# Sensor.net
KiCad netlist of a schematic drawn in Altium Designer
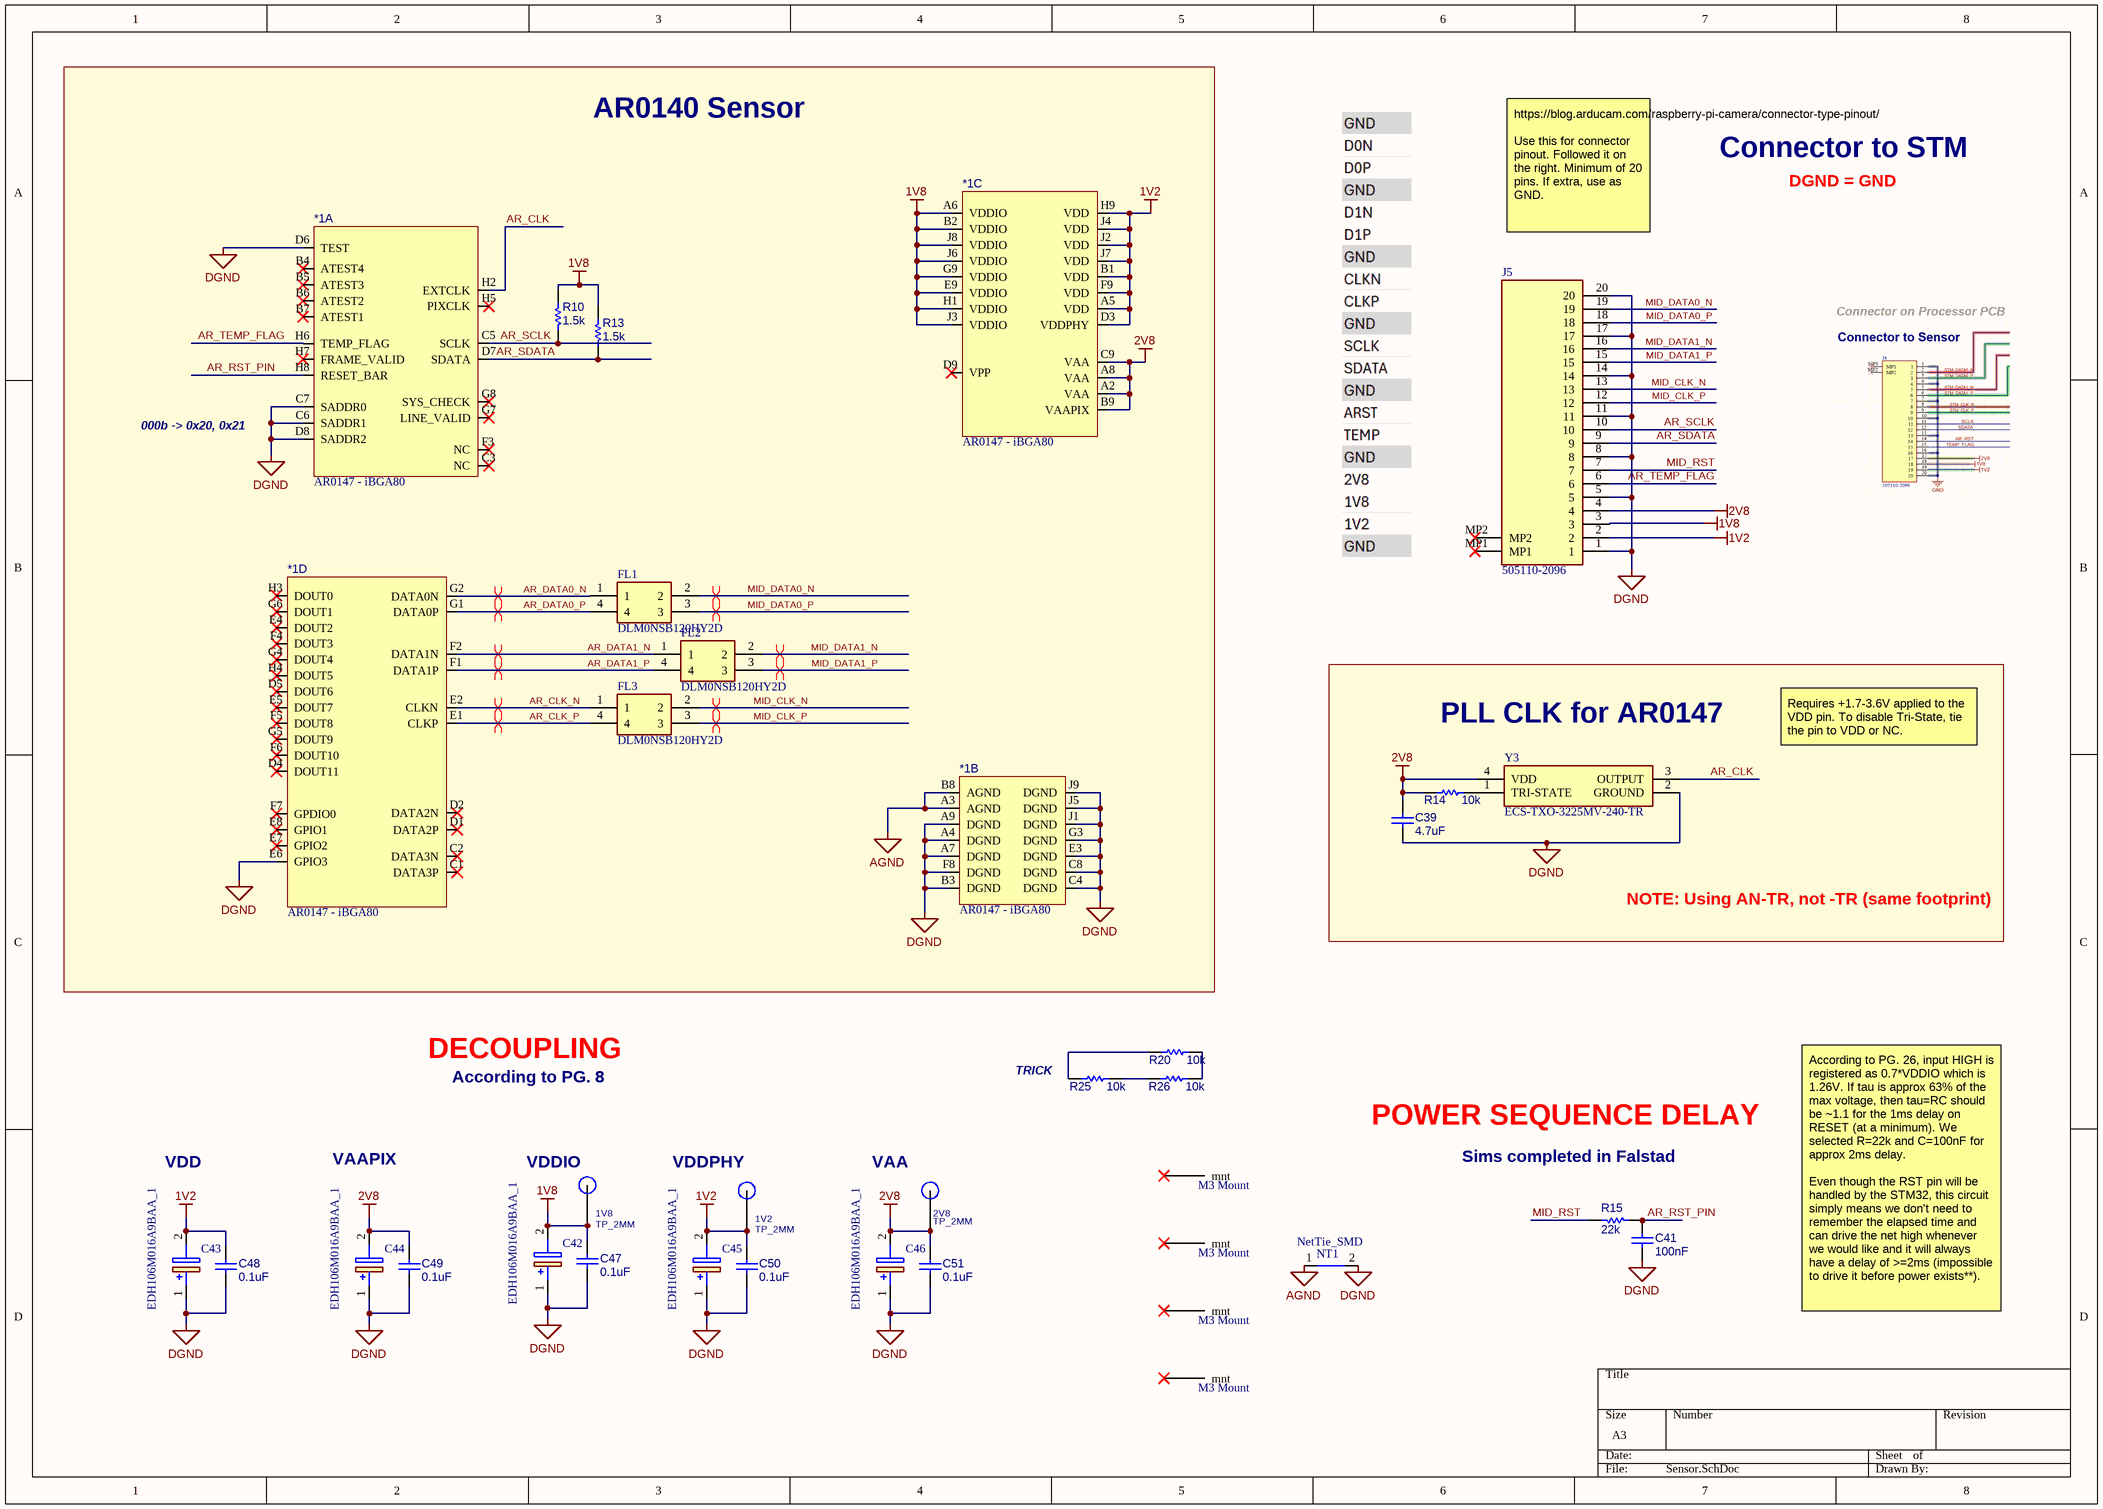
[diagram p0: Sensor.SchDoc]

(export (version "E")
  (design (tool "Eeschema 10.0.6"))
  (components
    (comp (ref "*1")
      (value "AR0147 - iBGA80")
      (footprint "AR0147 - IBGA80")
      (libsource (lib "C2S") (part "AR0147 - iBGA80"))
    )
    (comp (ref "1V2")
      (value "TP_2MM")
      (footprint "TESTPOINT 2MM")
      (libsource (lib "C2Sv0 - Processor") (part "TP_2MM"))
    )
    (comp (ref "1V8")
      (value "TP_2MM")
      (footprint "TESTPOINT 2MM")
      (libsource (lib "C2Sv0 - Processor") (part "TP_2MM"))
    )
    (comp (ref "2V8")
      (value "TP_2MM")
      (footprint "TESTPOINT 2MM")
      (libsource (lib "C2Sv0 - Processor") (part "TP_2MM"))
    )
    (comp (ref "C39")
      (value "4.7uF")
      (footprint "C0603")
      (description "Capacitor, MLCC, 100nF, 6V3, X5R, 10%, 0603, T=0,8mm")
      (fields
        (field (name "MANUFACTURER PART NUMBER") "CC0603KRX5R5BB104")
        (field (name "MANUFACTURER") "YAGEO")
        (field (name "PROVIDED_BY") "SUBCO")
      )
      (libsource (lib "Perth Aerospace Student Team") (part "CMP-035-000015-1"))
    )
    (comp (ref "C41")
      (value "100nF")
      (footprint "C0603")
      (description "Capacitor, MLCC, 100nF, 6V3, X5R, 10%, 0603, T=0,8mm")
      (fields
        (field (name "MANUFACTURER PART NUMBER") "CC0603KRX5R5BB104")
        (field (name "MANUFACTURER") "YAGEO")
        (field (name "PROVIDED_BY") "SUBCO")
      )
      (libsource (lib "Perth Aerospace Student Team") (part "CMP-035-000015-1"))
    )
    (comp (ref "C42")
      (value "EDH106M016A9BAA_1")
      (footprint "EDH106M016A9BAA")
      (description "Capacitor Polarised")
      (fields
        (field (name "MANUFACTURER_PART_NUMBER") "EDH106M016A9BAA")
        (field (name "MOUSER PART NUMBER") "80-EDH106M016A9BAA")
      )
      (libsource (lib "C2Sv0 - Processor") (part "EDH106M016A9BAA_1"))
    )
    (comp (ref "C43")
      (value "EDH106M016A9BAA_1")
      (footprint "EDH106M016A9BAA")
      (description "Capacitor Polarised")
      (fields
        (field (name "MANUFACTURER_PART_NUMBER") "EDH106M016A9BAA")
        (field (name "MOUSER PART NUMBER") "80-EDH106M016A9BAA")
      )
      (libsource (lib "C2Sv0 - Processor") (part "EDH106M016A9BAA_1"))
    )
    (comp (ref "C44")
      (value "EDH106M016A9BAA_1")
      (footprint "EDH106M016A9BAA")
      (description "Capacitor Polarised")
      (fields
        (field (name "MANUFACTURER_PART_NUMBER") "EDH106M016A9BAA")
        (field (name "MOUSER PART NUMBER") "80-EDH106M016A9BAA")
      )
      (libsource (lib "C2Sv0 - Processor") (part "EDH106M016A9BAA_1"))
    )
    (comp (ref "C45")
      (value "EDH106M016A9BAA_1")
      (footprint "EDH106M016A9BAA")
      (description "Capacitor Polarised")
      (fields
        (field (name "MANUFACTURER_PART_NUMBER") "EDH106M016A9BAA")
        (field (name "MOUSER PART NUMBER") "80-EDH106M016A9BAA")
      )
      (libsource (lib "C2Sv0 - Processor") (part "EDH106M016A9BAA_1"))
    )
    (comp (ref "C46")
      (value "EDH106M016A9BAA_1")
      (footprint "EDH106M016A9BAA")
      (description "Capacitor Polarised")
      (fields
        (field (name "MANUFACTURER_PART_NUMBER") "EDH106M016A9BAA")
        (field (name "MOUSER PART NUMBER") "80-EDH106M016A9BAA")
      )
      (libsource (lib "C2Sv0 - Processor") (part "EDH106M016A9BAA_1"))
    )
    (comp (ref "C47")
      (value "0.1uF")
      (footprint "C0603")
      (description "Capacitor, MLCC, 100nF, 6V3, X5R, 10%, 0603, T=0,8mm")
      (fields
        (field (name "MANUFACTURER PART NUMBER") "CC0603KRX5R5BB104")
        (field (name "MANUFACTURER") "YAGEO")
        (field (name "PROVIDED_BY") "SUBCO")
      )
      (libsource (lib "Perth Aerospace Student Team") (part "CMP-035-000015-1"))
    )
    (comp (ref "C48")
      (value "0.1uF")
      (footprint "C0603")
      (description "Capacitor, MLCC, 100nF, 6V3, X5R, 10%, 0603, T=0,8mm")
      (fields
        (field (name "MANUFACTURER PART NUMBER") "CC0603KRX5R5BB104")
        (field (name "MANUFACTURER") "YAGEO")
        (field (name "PROVIDED_BY") "SUBCO")
      )
      (libsource (lib "Perth Aerospace Student Team") (part "CMP-035-000015-1"))
    )
    (comp (ref "C49")
      (value "0.1uF")
      (footprint "C0603")
      (description "Capacitor, MLCC, 100nF, 6V3, X5R, 10%, 0603, T=0,8mm")
      (fields
        (field (name "MANUFACTURER PART NUMBER") "CC0603KRX5R5BB104")
        (field (name "MANUFACTURER") "YAGEO")
        (field (name "PROVIDED_BY") "SUBCO")
      )
      (libsource (lib "Perth Aerospace Student Team") (part "CMP-035-000015-1"))
    )
    (comp (ref "C50")
      (value "0.1uF")
      (footprint "C0603")
      (description "Capacitor, MLCC, 100nF, 6V3, X5R, 10%, 0603, T=0,8mm")
      (fields
        (field (name "MANUFACTURER PART NUMBER") "CC0603KRX5R5BB104")
        (field (name "MANUFACTURER") "YAGEO")
        (field (name "PROVIDED_BY") "SUBCO")
      )
      (libsource (lib "Perth Aerospace Student Team") (part "CMP-035-000015-1"))
    )
    (comp (ref "C51")
      (value "0.1uF")
      (footprint "C0603")
      (description "Capacitor, MLCC, 100nF, 6V3, X5R, 10%, 0603, T=0,8mm")
      (fields
        (field (name "MANUFACTURER PART NUMBER") "CC0603KRX5R5BB104")
        (field (name "MANUFACTURER") "YAGEO")
        (field (name "PROVIDED_BY") "SUBCO")
      )
      (libsource (lib "Perth Aerospace Student Team") (part "CMP-035-000015-1"))
    )
    (comp (ref "FL1")
      (value "DLM0NSB120HY2D")
      (footprint "DLM0NSB120HY2D")
      (description "Filter")
      (fields (field (name "MOUSER PART NUMBER") "81-DLM0NSB120HY2D"))
      (libsource (lib "C2Sv0 - Sensor") (part "DLM0NSB120HY2D"))
    )
    (comp (ref "FL2")
      (value "DLM0NSB120HY2D")
      (footprint "DLM0NSB120HY2D")
      (description "Filter")
      (fields (field (name "MOUSER PART NUMBER") "81-DLM0NSB120HY2D"))
      (libsource (lib "C2Sv0 - Sensor") (part "DLM0NSB120HY2D"))
    )
    (comp (ref "FL3")
      (value "DLM0NSB120HY2D")
      (footprint "DLM0NSB120HY2D")
      (description "Filter")
      (fields (field (name "MOUSER PART NUMBER") "81-DLM0NSB120HY2D"))
      (libsource (lib "C2Sv0 - Sensor") (part "DLM0NSB120HY2D"))
    )
    (comp (ref "J5")
      (value "505110-2096")
      (footprint "5051102096")
      (description "Connector")
      (fields (field (name "MOUSER PART NUMBER") "538-505110-2096"))
      (libsource (lib "C2S") (part "505110-2096"))
    )
    (comp (ref "MNT4")
      (value "M3 Mount")
      (footprint "M3_Mount-Footprint-1")
      (description "M3 mounting hole")
      (fields (field (name "AUTHOR") "Raphael Ho"))
      (libsource (lib "Perth Aerospace Student Team") (part "M3_Mount-Symbol-1"))
    )
    (comp (ref "MNT5")
      (value "M3 Mount")
      (footprint "M3_Mount-Footprint-1")
      (description "M3 mounting hole")
      (fields (field (name "AUTHOR") "Raphael Ho"))
      (libsource (lib "Perth Aerospace Student Team") (part "M3_Mount-Symbol-1"))
    )
    (comp (ref "MNT6")
      (value "M3 Mount")
      (footprint "M3_Mount-Footprint-1")
      (description "M3 mounting hole")
      (fields (field (name "AUTHOR") "Raphael Ho"))
      (libsource (lib "Perth Aerospace Student Team") (part "M3_Mount-Symbol-1"))
    )
    (comp (ref "MNT7")
      (value "M3 Mount")
      (footprint "M3_Mount-Footprint-1")
      (description "M3 mounting hole")
      (fields (field (name "AUTHOR") "Raphael Ho"))
      (libsource (lib "Perth Aerospace Student Team") (part "M3_Mount-Symbol-1"))
    )
    (comp (ref "NT1")
      (value "NetTie_SMD")
      (footprint "NETTIE_SMD")
      (description "Net Tie SMD")
      (fields (field (name "SOURCE") "Schematic-Lib-PhilsLab.SchLib"))
      (libsource (lib "Perth Aerospace Student Team") (part "NetTie_SMD"))
    )
    (comp (ref "R10")
      (value "1.5k")
      (footprint "RESC1608X55X25ML10T15-1")
      (description "Chip Resistor, 10k Ohm, 0.1 W, -55 to 155 degC, 0603 (1608 Metric)")
      (fields
        (field (name "POWER") "100mW")
        (field (name "TOLERANCE") "1%")
        (field (name "CREATED BY") "Micah Randall")
      )
      (libsource (lib "Perth Aerospace Student Team") (part "CMP-009-00006-5"))
    )
    (comp (ref "R13")
      (value "1.5k")
      (footprint "RESC1608X55X25ML10T15-1")
      (description "Chip Resistor, 10k Ohm, 0.1 W, -55 to 155 degC, 0603 (1608 Metric)")
      (fields
        (field (name "POWER") "100mW")
        (field (name "TOLERANCE") "1%")
        (field (name "CREATED BY") "Micah Randall")
      )
      (libsource (lib "Perth Aerospace Student Team") (part "CMP-009-00006-5"))
    )
    (comp (ref "R14")
      (value "10k")
      (footprint "RESC1608X55X25ML10T15-1")
      (description "Chip Resistor, 10k Ohm, 0.1 W, -55 to 155 degC, 0603 (1608 Metric)")
      (fields
        (field (name "POWER") "100mW")
        (field (name "TOLERANCE") "1%")
        (field (name "CREATED BY") "Micah Randall")
      )
      (libsource (lib "Perth Aerospace Student Team") (part "CMP-009-00006-5"))
    )
    (comp (ref "R15")
      (value "22k")
      (footprint "RESC1608X55X25ML10T15-1")
      (description "Chip Resistor, 10k Ohm, 0.1 W, -55 to 155 degC, 0603 (1608 Metric)")
      (fields
        (field (name "POWER") "100mW")
        (field (name "TOLERANCE") "1%")
        (field (name "CREATED BY") "Micah Randall")
      )
      (libsource (lib "Perth Aerospace Student Team") (part "CMP-009-00006-5"))
    )
    (comp (ref "R20")
      (value "10k")
      (footprint "RESC1608X55X25ML10T15-1")
      (description "Chip Resistor, 10k Ohm, 0.1 W, -55 to 155 degC, 0603 (1608 Metric)")
      (fields
        (field (name "POWER") "100mW")
        (field (name "TOLERANCE") "1%")
        (field (name "CREATED BY") "Micah Randall")
      )
      (libsource (lib "Perth Aerospace Student Team") (part "CMP-009-00006-5"))
    )
    (comp (ref "R25")
      (value "10k")
      (footprint "RESC1608X55X25ML10T15-1")
      (description "Chip Resistor, 10k Ohm, 0.1 W, -55 to 155 degC, 0603 (1608 Metric)")
      (fields
        (field (name "POWER") "100mW")
        (field (name "TOLERANCE") "1%")
        (field (name "CREATED BY") "Micah Randall")
      )
      (libsource (lib "Perth Aerospace Student Team") (part "CMP-009-00006-5"))
    )
    (comp (ref "R26")
      (value "10k")
      (footprint "RESC1608X55X25ML10T15-1")
      (description "Chip Resistor, 10k Ohm, 0.1 W, -55 to 155 degC, 0603 (1608 Metric)")
      (fields
        (field (name "POWER") "100mW")
        (field (name "TOLERANCE") "1%")
        (field (name "CREATED BY") "Micah Randall")
      )
      (libsource (lib "Perth Aerospace Student Team") (part "CMP-009-00006-5"))
    )
    (comp (ref "Y3")
      (value "ECS-TXO-3225MV-240-TR")
      (footprint "ECSTXO3225MV240TR")
      (description "Crystal or Oscillator")
      (fields (field (name "MOUSER PART NUMBER") "520-TXO-3225MV-240-T"))
      (libsource (lib "C2Sv0 - Processor") (part "ECS-TXO-3225MV-240-TR"))
    )
  )
  (nets
    (net (code "1") (name "/AR_CLK") (class "Default")
      (node (ref "*1") (pin "H2") (pinfunction "EXTCLK_H2") (pintype "input"))
      (node (ref "Y3") (pin "3") (pinfunction "OUTPUT_3") (pintype "passive"))
    )
    (net (code "2") (name "/AR_CLK_N") (class "Default")
      (node (ref "*1") (pin "E2") (pinfunction "CLKN_E2") (pintype "output"))
      (node (ref "FL3") (pin "1") (pinfunction "1_1") (pintype "passive"))
    )
    (net (code "3") (name "/AR_CLK_P") (class "Default")
      (node (ref "*1") (pin "E1") (pinfunction "CLKP_E1") (pintype "output"))
      (node (ref "FL3") (pin "4") (pinfunction "4_4") (pintype "passive"))
    )
    (net (code "4") (name "/AR_DATA0_N") (class "Default")
      (node (ref "*1") (pin "G2") (pinfunction "DATA0N_G2") (pintype "output"))
      (node (ref "FL1") (pin "1") (pinfunction "1_1") (pintype "passive"))
    )
    (net (code "5") (name "/AR_DATA0_P") (class "Default")
      (node (ref "*1") (pin "G1") (pinfunction "DATA0P_G1") (pintype "output"))
      (node (ref "FL1") (pin "4") (pinfunction "4_4") (pintype "passive"))
    )
    (net (code "6") (name "/AR_DATA1_N") (class "Default")
      (node (ref "*1") (pin "F2") (pinfunction "DATA1N_F2") (pintype "output"))
      (node (ref "FL2") (pin "1") (pinfunction "1_1") (pintype "passive"))
    )
    (net (code "7") (name "/AR_DATA1_P") (class "Default")
      (node (ref "*1") (pin "F1") (pinfunction "DATA1P_F1") (pintype "output"))
      (node (ref "FL2") (pin "4") (pinfunction "4_4") (pintype "passive"))
    )
    (net (code "8") (name "/AR_RST_PIN") (class "Default")
      (node (ref "*1") (pin "H8") (pinfunction "RESET_BAR_H8") (pintype "input"))
      (node (ref "C41") (pin "2") (pinfunction "2_2") (pintype "passive"))
      (node (ref "R15") (pin "2") (pinfunction "2_2") (pintype "passive"))
    )
    (net (code "9") (name "/AR_SCLK") (class "Default")
      (node (ref "*1") (pin "C5") (pinfunction "SCLK_C5") (pintype "input"))
      (node (ref "J5") (pin "10") (pinfunction "10_10") (pintype "passive"))
      (node (ref "R10") (pin "2") (pinfunction "2_2") (pintype "passive"))
    )
    (net (code "10") (name "/AR_SDATA") (class "Default")
      (node (ref "*1") (pin "D7") (pinfunction "SDATA_D7") (pintype "input"))
      (node (ref "J5") (pin "9") (pinfunction "9_9") (pintype "passive"))
      (node (ref "R13") (pin "2") (pinfunction "2_2") (pintype "passive"))
    )
    (net (code "11") (name "/AR_TEMP_FLAG") (class "Default")
      (node (ref "*1") (pin "H6") (pinfunction "TEMP_FLAG_H6") (pintype "output"))
      (node (ref "J5") (pin "6") (pinfunction "6_6") (pintype "passive"))
    )
    (net (code "12") (name "/MID_CLK_N") (class "Default")
      (node (ref "FL3") (pin "2") (pinfunction "2_2") (pintype "passive"))
      (node (ref "J5") (pin "13") (pinfunction "13_13") (pintype "passive"))
    )
    (net (code "13") (name "/MID_CLK_P") (class "Default")
      (node (ref "FL3") (pin "3") (pinfunction "3_3") (pintype "passive"))
      (node (ref "J5") (pin "12") (pinfunction "12_12") (pintype "passive"))
    )
    (net (code "14") (name "/MID_DATA0_N") (class "Default")
      (node (ref "FL1") (pin "2") (pinfunction "2_2") (pintype "passive"))
      (node (ref "J5") (pin "19") (pinfunction "19_19") (pintype "passive"))
    )
    (net (code "15") (name "/MID_DATA0_P") (class "Default")
      (node (ref "FL1") (pin "3") (pinfunction "3_3") (pintype "passive"))
      (node (ref "J5") (pin "18") (pinfunction "18_18") (pintype "passive"))
    )
    (net (code "16") (name "/MID_DATA1_N") (class "Default")
      (node (ref "FL2") (pin "2") (pinfunction "2_2") (pintype "passive"))
      (node (ref "J5") (pin "16") (pinfunction "16_16") (pintype "passive"))
    )
    (net (code "17") (name "/MID_DATA1_P") (class "Default")
      (node (ref "FL2") (pin "3") (pinfunction "3_3") (pintype "passive"))
      (node (ref "J5") (pin "15") (pinfunction "15_15") (pintype "passive"))
    )
    (net (code "18") (name "/MID_RST") (class "Default")
      (node (ref "J5") (pin "7") (pinfunction "7_7") (pintype "passive"))
      (node (ref "R15") (pin "1") (pinfunction "1_1") (pintype "passive"))
    )
    (net (code "19") (name "1V2") (class "Default")
      (node (ref "*1") (pin "A5") (pinfunction "VDD_A5") (pintype "power_in"))
      (node (ref "*1") (pin "B1") (pinfunction "VDD_B1") (pintype "power_in"))
      (node (ref "*1") (pin "D3") (pinfunction "VDDPHY_D3") (pintype "power_in"))
      (node (ref "*1") (pin "F9") (pinfunction "VDD_F9") (pintype "power_in"))
      (node (ref "*1") (pin "H9") (pinfunction "VDD_H9") (pintype "power_in"))
      (node (ref "*1") (pin "J2") (pinfunction "VDD_J2") (pintype "power_in"))
      (node (ref "*1") (pin "J4") (pinfunction "VDD_J4") (pintype "power_in"))
      (node (ref "*1") (pin "J7") (pinfunction "VDD_J7") (pintype "power_in"))
      (node (ref "1V2") (pin "TP") (pinfunction "TP_2MM_TP") (pintype "passive"))
      (node (ref "C43") (pin "2") (pinfunction "-_2") (pintype "passive"))
      (node (ref "C45") (pin "2") (pinfunction "-_2") (pintype "passive"))
      (node (ref "C48") (pin "2") (pinfunction "2_2") (pintype "passive"))
      (node (ref "C50") (pin "2") (pinfunction "2_2") (pintype "passive"))
      (node (ref "J5") (pin "2") (pinfunction "2_2") (pintype "passive"))
    )
    (net (code "20") (name "1V8") (class "Default")
      (node (ref "*1") (pin "A6") (pinfunction "VDDIO_A6") (pintype "power_in"))
      (node (ref "*1") (pin "B2") (pinfunction "VDDIO_B2") (pintype "power_in"))
      (node (ref "*1") (pin "E9") (pinfunction "VDDIO_E9") (pintype "power_in"))
      (node (ref "*1") (pin "G9") (pinfunction "VDDIO_G9") (pintype "power_in"))
      (node (ref "*1") (pin "H1") (pinfunction "VDDIO_H1") (pintype "power_in"))
      (node (ref "*1") (pin "J3") (pinfunction "VDDIO_J3") (pintype "power_in"))
      (node (ref "*1") (pin "J6") (pinfunction "VDDIO_J6") (pintype "power_in"))
      (node (ref "*1") (pin "J8") (pinfunction "VDDIO_J8") (pintype "power_in"))
      (node (ref "1V8") (pin "TP") (pinfunction "TP_2MM_TP") (pintype "passive"))
      (node (ref "C42") (pin "2") (pinfunction "-_2") (pintype "passive"))
      (node (ref "C47") (pin "2") (pinfunction "2_2") (pintype "passive"))
      (node (ref "J5") (pin "3") (pinfunction "3_3") (pintype "passive"))
      (node (ref "R10") (pin "1") (pinfunction "1_1") (pintype "passive"))
      (node (ref "R13") (pin "1") (pinfunction "1_1") (pintype "passive"))
    )
    (net (code "21") (name "2V8") (class "Default")
      (node (ref "*1") (pin "A2") (pinfunction "VAA_A2") (pintype "power_in"))
      (node (ref "*1") (pin "A8") (pinfunction "VAA_A8") (pintype "power_in"))
      (node (ref "*1") (pin "B9") (pinfunction "VAAPIX_B9") (pintype "power_in"))
      (node (ref "*1") (pin "C9") (pinfunction "VAA_C9") (pintype "power_in"))
      (node (ref "2V8") (pin "TP") (pinfunction "TP_2MM_TP") (pintype "passive"))
      (node (ref "C39") (pin "2") (pinfunction "2_2") (pintype "passive"))
      (node (ref "C44") (pin "2") (pinfunction "-_2") (pintype "passive"))
      (node (ref "C46") (pin "2") (pinfunction "-_2") (pintype "passive"))
      (node (ref "C49") (pin "2") (pinfunction "2_2") (pintype "passive"))
      (node (ref "C51") (pin "2") (pinfunction "2_2") (pintype "passive"))
      (node (ref "J5") (pin "4") (pinfunction "4_4") (pintype "passive"))
      (node (ref "R14") (pin "1") (pinfunction "1_1") (pintype "passive"))
      (node (ref "Y3") (pin "4") (pinfunction "VDD_4") (pintype "passive"))
    )
    (net (code "22") (name "AGND") (class "Default")
      (node (ref "*1") (pin "A3") (pinfunction "AGND_A3") (pintype "power_in"))
      (node (ref "*1") (pin "B8") (pinfunction "AGND_B8") (pintype "power_in"))
      (node (ref "NT1") (pin "1") (pinfunction "1_1") (pintype "passive"))
    )
    (net (code "23") (name "DGND") (class "Default")
      (node (ref "*1") (pin "A4") (pinfunction "DGND_A4") (pintype "power_in"))
      (node (ref "*1") (pin "A7") (pinfunction "DGND_A7") (pintype "power_in"))
      (node (ref "*1") (pin "A9") (pinfunction "DGND_A9") (pintype "power_in"))
      (node (ref "*1") (pin "B3") (pinfunction "DGND_B3") (pintype "power_in"))
      (node (ref "*1") (pin "C4") (pinfunction "DGND_C4") (pintype "power_in"))
      (node (ref "*1") (pin "C6") (pinfunction "SADDR1_C6") (pintype "input"))
      (node (ref "*1") (pin "C7") (pinfunction "SADDR0_C7") (pintype "input"))
      (node (ref "*1") (pin "C8") (pinfunction "DGND_C8") (pintype "power_in"))
      (node (ref "*1") (pin "D6") (pinfunction "TEST_D6") (pintype "passive"))
      (node (ref "*1") (pin "D8") (pinfunction "SADDR2_D8") (pintype "input"))
      (node (ref "*1") (pin "E3") (pinfunction "DGND_E3") (pintype "power_in"))
      (node (ref "*1") (pin "E6") (pinfunction "GPIO3_E6") (pintype "bidirectional"))
      (node (ref "*1") (pin "F8") (pinfunction "DGND_F8") (pintype "power_in"))
      (node (ref "*1") (pin "G3") (pinfunction "DGND_G3") (pintype "power_in"))
      (node (ref "*1") (pin "J1") (pinfunction "DGND_J1") (pintype "power_in"))
      (node (ref "*1") (pin "J5") (pinfunction "DGND_J5") (pintype "power_in"))
      (node (ref "*1") (pin "J9") (pinfunction "DGND_J9") (pintype "power_in"))
      (node (ref "C39") (pin "1") (pinfunction "1_1") (pintype "passive"))
      (node (ref "C41") (pin "1") (pinfunction "1_1") (pintype "passive"))
      (node (ref "C42") (pin "1") (pinfunction "+_1") (pintype "passive"))
      (node (ref "C43") (pin "1") (pinfunction "+_1") (pintype "passive"))
      (node (ref "C44") (pin "1") (pinfunction "+_1") (pintype "passive"))
      (node (ref "C45") (pin "1") (pinfunction "+_1") (pintype "passive"))
      (node (ref "C46") (pin "1") (pinfunction "+_1") (pintype "passive"))
      (node (ref "C47") (pin "1") (pinfunction "1_1") (pintype "passive"))
      (node (ref "C48") (pin "1") (pinfunction "1_1") (pintype "passive"))
      (node (ref "C49") (pin "1") (pinfunction "1_1") (pintype "passive"))
      (node (ref "C50") (pin "1") (pinfunction "1_1") (pintype "passive"))
      (node (ref "C51") (pin "1") (pinfunction "1_1") (pintype "passive"))
      (node (ref "J5") (pin "1") (pinfunction "1_1") (pintype "passive"))
      (node (ref "J5") (pin "11") (pinfunction "11_11") (pintype "passive"))
      (node (ref "J5") (pin "14") (pinfunction "14_14") (pintype "passive"))
      (node (ref "J5") (pin "17") (pinfunction "17_17") (pintype "passive"))
      (node (ref "J5") (pin "20") (pinfunction "20_20") (pintype "passive"))
      (node (ref "J5") (pin "5") (pinfunction "5_5") (pintype "passive"))
      (node (ref "J5") (pin "8") (pinfunction "8_8") (pintype "passive"))
      (node (ref "NT1") (pin "2") (pinfunction "2_2") (pintype "passive"))
      (node (ref "Y3") (pin "2") (pinfunction "GROUND_2") (pintype "passive"))
    )
    (net (code "24") (name "Net-(R20-Pad1)") (class "Default")
      (node (ref "R20") (pin "1") (pinfunction "1_1") (pintype "passive"))
      (node (ref "R25") (pin "1") (pinfunction "1_1") (pintype "passive"))
    )
    (net (code "25") (name "Net-(R20-Pad2)") (class "Default")
      (node (ref "R20") (pin "2") (pinfunction "2_2") (pintype "passive"))
      (node (ref "R26") (pin "2") (pinfunction "2_2") (pintype "passive"))
    )
    (net (code "26") (name "Net-(R25-Pad2)") (class "Default")
      (node (ref "R25") (pin "2") (pinfunction "2_2") (pintype "passive"))
      (node (ref "R26") (pin "1") (pinfunction "1_1") (pintype "passive"))
    )
    (net (code "27") (name "Net-(Y3-TRI-STATE)") (class "Default")
      (node (ref "R14") (pin "2") (pinfunction "2_2") (pintype "passive"))
      (node (ref "Y3") (pin "1") (pinfunction "TRI-STATE_1") (pintype "passive"))
    )
    (net (code "28") (name "unconnected-(*1A-ATEST1-PadB7)") (class "Default")
      (node (ref "*1") (pin "B7") (pinfunction "ATEST1_B7") (pintype "passive+no_connect"))
    )
    (net (code "29") (name "unconnected-(*1A-ATEST2-PadB6)") (class "Default")
      (node (ref "*1") (pin "B6") (pinfunction "ATEST2_B6") (pintype "passive+no_connect"))
    )
    (net (code "30") (name "unconnected-(*1A-ATEST3-PadB5)") (class "Default")
      (node (ref "*1") (pin "B5") (pinfunction "ATEST3_B5") (pintype "passive+no_connect"))
    )
    (net (code "31") (name "unconnected-(*1A-ATEST4-PadB4)") (class "Default")
      (node (ref "*1") (pin "B4") (pinfunction "ATEST4_B4") (pintype "passive+no_connect"))
    )
    (net (code "32") (name "unconnected-(*1A-FRAME_VALID-PadH7)") (class "Default")
      (node (ref "*1") (pin "H7") (pinfunction "FRAME_VALID_H7") (pintype "output+no_connect"))
    )
    (net (code "33") (name "unconnected-(*1A-LINE_VALID-PadG7)") (class "Default")
      (node (ref "*1") (pin "G7") (pinfunction "LINE_VALID_G7") (pintype "output+no_connect"))
    )
    (net (code "34") (name "unconnected-(*1A-NC-PadC3)") (class "Default")
      (node (ref "*1") (pin "C3") (pinfunction "NC_C3") (pintype "passive+no_connect"))
    )
    (net (code "35") (name "unconnected-(*1A-NC-PadF3)") (class "Default")
      (node (ref "*1") (pin "F3") (pinfunction "NC_F3") (pintype "passive+no_connect"))
    )
    (net (code "36") (name "unconnected-(*1A-PIXCLK-PadH5)") (class "Default")
      (node (ref "*1") (pin "H5") (pinfunction "PIXCLK_H5") (pintype "output+no_connect"))
    )
    (net (code "37") (name "unconnected-(*1A-SYS_CHECK-PadG8)") (class "Default")
      (node (ref "*1") (pin "G8") (pinfunction "SYS_CHECK_G8") (pintype "output+no_connect"))
    )
    (net (code "38") (name "unconnected-(*1C-VPP-PadD9)") (class "Default")
      (node (ref "*1") (pin "D9") (pinfunction "VPP_D9") (pintype "power_in+no_connect"))
    )
    (net (code "39") (name "unconnected-(*1D-DATA2N-PadD2)") (class "Default")
      (node (ref "*1") (pin "D2") (pinfunction "DATA2N_D2") (pintype "output+no_connect"))
    )
    (net (code "40") (name "unconnected-(*1D-DATA2P-PadD1)") (class "Default")
      (node (ref "*1") (pin "D1") (pinfunction "DATA2P_D1") (pintype "output+no_connect"))
    )
    (net (code "41") (name "unconnected-(*1D-DATA3N-PadC2)") (class "Default")
      (node (ref "*1") (pin "C2") (pinfunction "DATA3N_C2") (pintype "output+no_connect"))
    )
    (net (code "42") (name "unconnected-(*1D-DATA3P-PadC1)") (class "Default")
      (node (ref "*1") (pin "C1") (pinfunction "DATA3P_C1") (pintype "output+no_connect"))
    )
    (net (code "43") (name "unconnected-(*1D-DOUT0-PadH3)") (class "Default")
      (node (ref "*1") (pin "H3") (pinfunction "DOUT0_H3") (pintype "output+no_connect"))
    )
    (net (code "44") (name "unconnected-(*1D-DOUT1-PadG6)") (class "Default")
      (node (ref "*1") (pin "G6") (pinfunction "DOUT1_G6") (pintype "output+no_connect"))
    )
    (net (code "45") (name "unconnected-(*1D-DOUT2-PadE4)") (class "Default")
      (node (ref "*1") (pin "E4") (pinfunction "DOUT2_E4") (pintype "output+no_connect"))
    )
    (net (code "46") (name "unconnected-(*1D-DOUT3-PadF4)") (class "Default")
      (node (ref "*1") (pin "F4") (pinfunction "DOUT3_F4") (pintype "output+no_connect"))
    )
    (net (code "47") (name "unconnected-(*1D-DOUT4-PadG4)") (class "Default")
      (node (ref "*1") (pin "G4") (pinfunction "DOUT4_G4") (pintype "output+no_connect"))
    )
    (net (code "48") (name "unconnected-(*1D-DOUT5-PadH4)") (class "Default")
      (node (ref "*1") (pin "H4") (pinfunction "DOUT5_H4") (pintype "output+no_connect"))
    )
    (net (code "49") (name "unconnected-(*1D-DOUT6-PadD5)") (class "Default")
      (node (ref "*1") (pin "D5") (pinfunction "DOUT6_D5") (pintype "output+no_connect"))
    )
    (net (code "50") (name "unconnected-(*1D-DOUT7-PadE5)") (class "Default")
      (node (ref "*1") (pin "E5") (pinfunction "DOUT7_E5") (pintype "output+no_connect"))
    )
    (net (code "51") (name "unconnected-(*1D-DOUT8-PadF5)") (class "Default")
      (node (ref "*1") (pin "F5") (pinfunction "DOUT8_F5") (pintype "output+no_connect"))
    )
    (net (code "52") (name "unconnected-(*1D-DOUT9-PadG5)") (class "Default")
      (node (ref "*1") (pin "G5") (pinfunction "DOUT9_G5") (pintype "output+no_connect"))
    )
    (net (code "53") (name "unconnected-(*1D-DOUT10-PadF6)") (class "Default")
      (node (ref "*1") (pin "F6") (pinfunction "DOUT10_F6") (pintype "output+no_connect"))
    )
    (net (code "54") (name "unconnected-(*1D-DOUT11-PadD4)") (class "Default")
      (node (ref "*1") (pin "D4") (pinfunction "DOUT11_D4") (pintype "output+no_connect"))
    )
    (net (code "55") (name "unconnected-(*1D-GPDIO0-PadF7)") (class "Default")
      (node (ref "*1") (pin "F7") (pinfunction "GPDIO0_F7") (pintype "bidirectional+no_connect"))
    )
    (net (code "56") (name "unconnected-(*1D-GPIO1-PadE8)") (class "Default")
      (node (ref "*1") (pin "E8") (pinfunction "GPIO1_E8") (pintype "bidirectional+no_connect"))
    )
    (net (code "57") (name "unconnected-(*1D-GPIO2-PadE7)") (class "Default")
      (node (ref "*1") (pin "E7") (pinfunction "GPIO2_E7") (pintype "bidirectional+no_connect"))
    )
    (net (code "58") (name "unconnected-(J5-PadMP1)") (class "Default")
      (node (ref "J5") (pin "MP1") (pinfunction "MP1_MP1") (pintype "passive+no_connect"))
    )
    (net (code "59") (name "unconnected-(J5-PadMP2)") (class "Default")
      (node (ref "J5") (pin "MP2") (pinfunction "MP2_MP2") (pintype "passive+no_connect"))
    )
    (net (code "60") (name "unconnected-(MNT4-mnt-Pad1)") (class "Default")
      (node (ref "MNT4") (pin "1") (pinfunction "mnt_1") (pintype "passive+no_connect"))
    )
    (net (code "61") (name "unconnected-(MNT5-mnt-Pad1)") (class "Default")
      (node (ref "MNT5") (pin "1") (pinfunction "mnt_1") (pintype "passive+no_connect"))
    )
    (net (code "62") (name "unconnected-(MNT6-mnt-Pad1)") (class "Default")
      (node (ref "MNT6") (pin "1") (pinfunction "mnt_1") (pintype "passive+no_connect"))
    )
    (net (code "63") (name "unconnected-(MNT7-mnt-Pad1)") (class "Default")
      (node (ref "MNT7") (pin "1") (pinfunction "mnt_1") (pintype "passive+no_connect"))
    )
  )
)
